# HallSenseV2.net
KiCad netlist of a schematic drawn in EAGLE
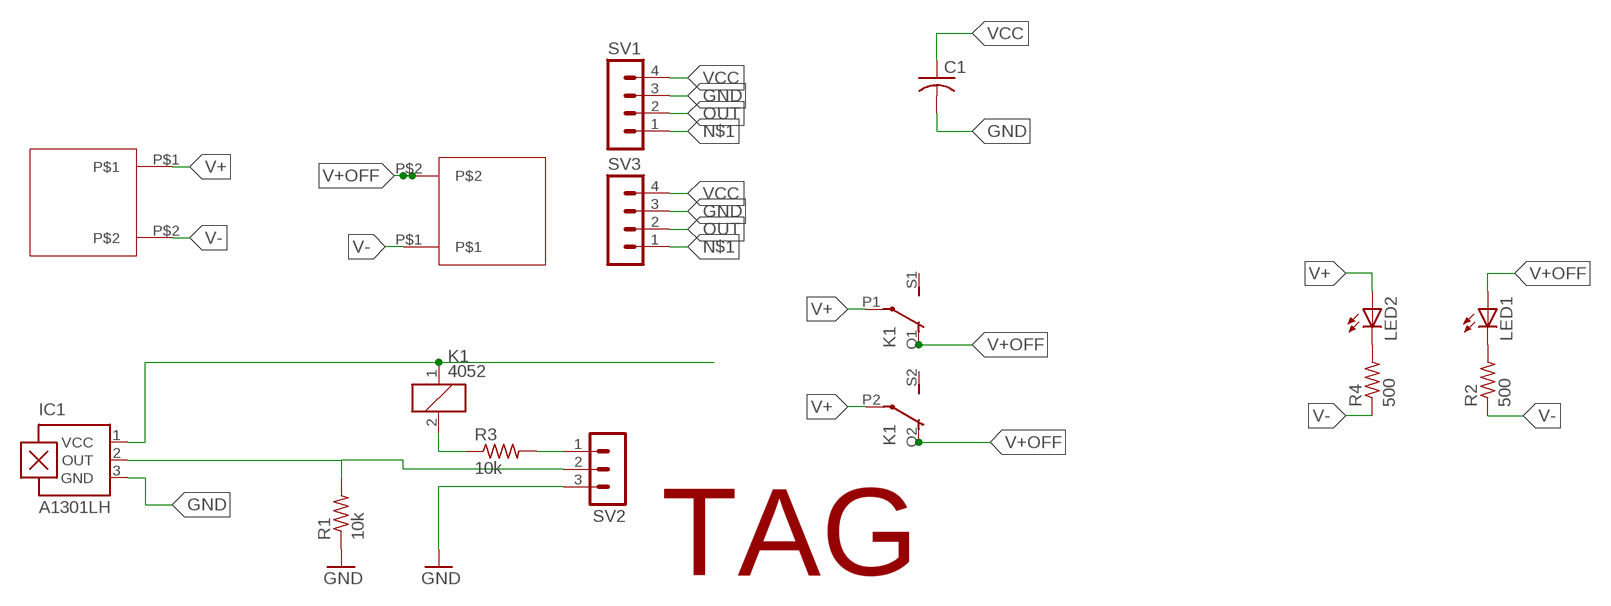
[diagram p0: schematic, sheet 1]

(export (version "E")
  (design (tool "Eeschema 10.0.6"))
  (components
    (comp (ref "C1")
      (value "C-USC0805K")
      (footprint "eagle-import:C0805K")
      (libsource (lib "eagle-import") (part "C-USC0805K"))
    )
    (comp (ref "IC1")
      (value "A1301LH")
      (footprint "eagle-import:SOT23-W")
      (fields (field (name "MF") "ALLEGRO MICROSYSTEMS, INC.") (field (name "MPN") "A1301ELHLT-T"))
      (libsource (lib "eagle-import") (part "A13?LH01"))
    )
    (comp (ref "K1")
      (value "4052")
      (footprint "eagle-import:F4052")
      (fields (field (name "SPICEPREFIX") "J"))
      (libsource (lib "eagle-import") (part "4052"))
    )
    (comp (ref "LED1")
      (value "LED5MM")
      (footprint "eagle-import:LED5MM")
      (libsource (lib "eagle-import") (part "LED5MM"))
    )
    (comp (ref "LED2")
      (value "LED5MM")
      (footprint "eagle-import:LED5MM")
      (libsource (lib "eagle-import") (part "LED5MM"))
    )
    (comp (ref "R1")
      (value "10k")
      (footprint "eagle-import:R0805")
      (libsource (lib "eagle-import") (part "resistor_348_R-US_R0805"))
    )
    (comp (ref "R2")
      (value "500")
      (footprint "eagle-import:0207_10")
      (libsource (lib "eagle-import") (part "R-US_0207/10"))
    )
    (comp (ref "R3")
      (value "10k")
      (footprint "eagle-import:R0805")
      (libsource (lib "eagle-import") (part "resistor_348_R-US_R0805"))
    )
    (comp (ref "R4")
      (value "500")
      (footprint "eagle-import:0207_10")
      (libsource (lib "eagle-import") (part "R-US_0207/10"))
    )
    (comp (ref "SV1")
      (value "MA04-1")
      (footprint "eagle-import:MA04-1")
      (libsource (lib "eagle-import") (part "MA04-1"))
    )
    (comp (ref "SV2")
      (value "MA03-1")
      (footprint "eagle-import:MA03-1")
      (libsource (lib "eagle-import") (part "MA03-1"))
    )
    (comp (ref "SV3")
      (value "MA04-1")
      (footprint "eagle-import:MA04-1")
      (libsource (lib "eagle-import") (part "MA04-1"))
    )
    (comp (ref "U$1")
      (value "TERM_POWER")
      (footprint "eagle-import:TERM_BLOCK_POWER")
      (libsource (lib "eagle-import") (part "TERM_POWER"))
    )
    (comp (ref "U$2")
      (value "TERM_POWER")
      (footprint "eagle-import:TERM_BLOCK_POWER")
      (libsource (lib "eagle-import") (part "TERM_POWER"))
    )
    (comp (ref "U$3")
      (value "TAG")
      (footprint "eagle-import:TAG")
      (libsource (lib "eagle-import") (part "TAG"))
    )
  )
  (nets
    (net (code "1") (name "GND") (class "Default")
      (node (ref "C1") (pin "2") (pinfunction "2_2") (pintype "passive"))
      (node (ref "IC1") (pin "3") (pinfunction "GND_3") (pintype "power_in"))
      (node (ref "R1") (pin "1") (pinfunction "1_1") (pintype "passive"))
      (node (ref "SV1") (pin "3") (pinfunction "3_3") (pintype "passive"))
      (node (ref "SV2") (pin "3") (pinfunction "3_3") (pintype "passive"))
      (node (ref "SV3") (pin "3") (pinfunction "3_3") (pintype "passive"))
    )
    (net (code "2") (name "N$1") (class "Default")
      (node (ref "K1") (pin "2") (pinfunction "2_2") (pintype "passive"))
      (node (ref "R3") (pin "1") (pinfunction "1_1") (pintype "passive"))
      (node (ref "SV1") (pin "1") (pinfunction "1_1") (pintype "passive"))
      (node (ref "SV3") (pin "1") (pinfunction "1_1") (pintype "passive"))
    )
    (net (code "3") (name "Net-(LED1-C)") (class "Default")
      (node (ref "LED1") (pin "K") (pinfunction "C_K") (pintype "passive"))
      (node (ref "R2") (pin "2") (pinfunction "2_2") (pintype "passive"))
    )
    (net (code "4") (name "Net-(LED2-C)") (class "Default")
      (node (ref "LED2") (pin "K") (pinfunction "C_K") (pintype "passive"))
      (node (ref "R4") (pin "2") (pinfunction "2_2") (pintype "passive"))
    )
    (net (code "5") (name "Net-(R3-Pad2)") (class "Default")
      (node (ref "R3") (pin "2") (pinfunction "2_2") (pintype "passive"))
      (node (ref "SV2") (pin "1") (pinfunction "1_1") (pintype "passive"))
    )
    (net (code "6") (name "OUT") (class "Default")
      (node (ref "IC1") (pin "2") (pinfunction "OUT_2") (pintype "output"))
      (node (ref "R1") (pin "2") (pinfunction "2_2") (pintype "passive"))
      (node (ref "SV1") (pin "2") (pinfunction "2_2") (pintype "passive"))
      (node (ref "SV2") (pin "2") (pinfunction "2_2") (pintype "passive"))
      (node (ref "SV3") (pin "2") (pinfunction "2_2") (pintype "passive"))
    )
    (net (code "7") (name "V+") (class "Default")
      (node (ref "K1") (pin "P1") (pinfunction "P_P1") (pintype "passive"))
      (node (ref "K1") (pin "P2") (pinfunction "P_P2") (pintype "passive"))
      (node (ref "LED2") (pin "A") (pinfunction "A_A") (pintype "passive"))
      (node (ref "U$1") (pin "P$1") (pinfunction "P$1_P$1") (pintype "bidirectional"))
    )
    (net (code "8") (name "V+OFF") (class "Default")
      (node (ref "K1") (pin "O1") (pinfunction "O_O1") (pintype "passive"))
      (node (ref "K1") (pin "O2") (pinfunction "O_O2") (pintype "passive"))
      (node (ref "LED1") (pin "A") (pinfunction "A_A") (pintype "passive"))
      (node (ref "U$2") (pin "P$2") (pinfunction "P$2_P$2") (pintype "bidirectional"))
    )
    (net (code "9") (name "V-") (class "Default")
      (node (ref "R2") (pin "1") (pinfunction "1_1") (pintype "passive"))
      (node (ref "R4") (pin "1") (pinfunction "1_1") (pintype "passive"))
      (node (ref "U$1") (pin "P$2") (pinfunction "P$2_P$2") (pintype "bidirectional"))
      (node (ref "U$2") (pin "P$1") (pinfunction "P$1_P$1") (pintype "bidirectional"))
    )
    (net (code "10") (name "VCC") (class "Default")
      (node (ref "C1") (pin "1") (pinfunction "1_1") (pintype "passive"))
      (node (ref "IC1") (pin "1") (pinfunction "VCC_1") (pintype "power_in"))
      (node (ref "K1") (pin "1") (pinfunction "1_1") (pintype "passive"))
      (node (ref "SV1") (pin "4") (pinfunction "4_4") (pintype "passive"))
      (node (ref "SV3") (pin "4") (pinfunction "4_4") (pintype "passive"))
    )
    (net (code "11") (name "unconnected-(K1B-S-PadS1)") (class "Default")
      (node (ref "K1") (pin "S1") (pinfunction "S_S1") (pintype "passive"))
    )
    (net (code "12") (name "unconnected-(K1C-S-PadS2)") (class "Default")
      (node (ref "K1") (pin "S2") (pinfunction "S_S2") (pintype "passive"))
    )
  )
)
